# S202E.net
KiCad netlist of a schematic drawn in EAGLE
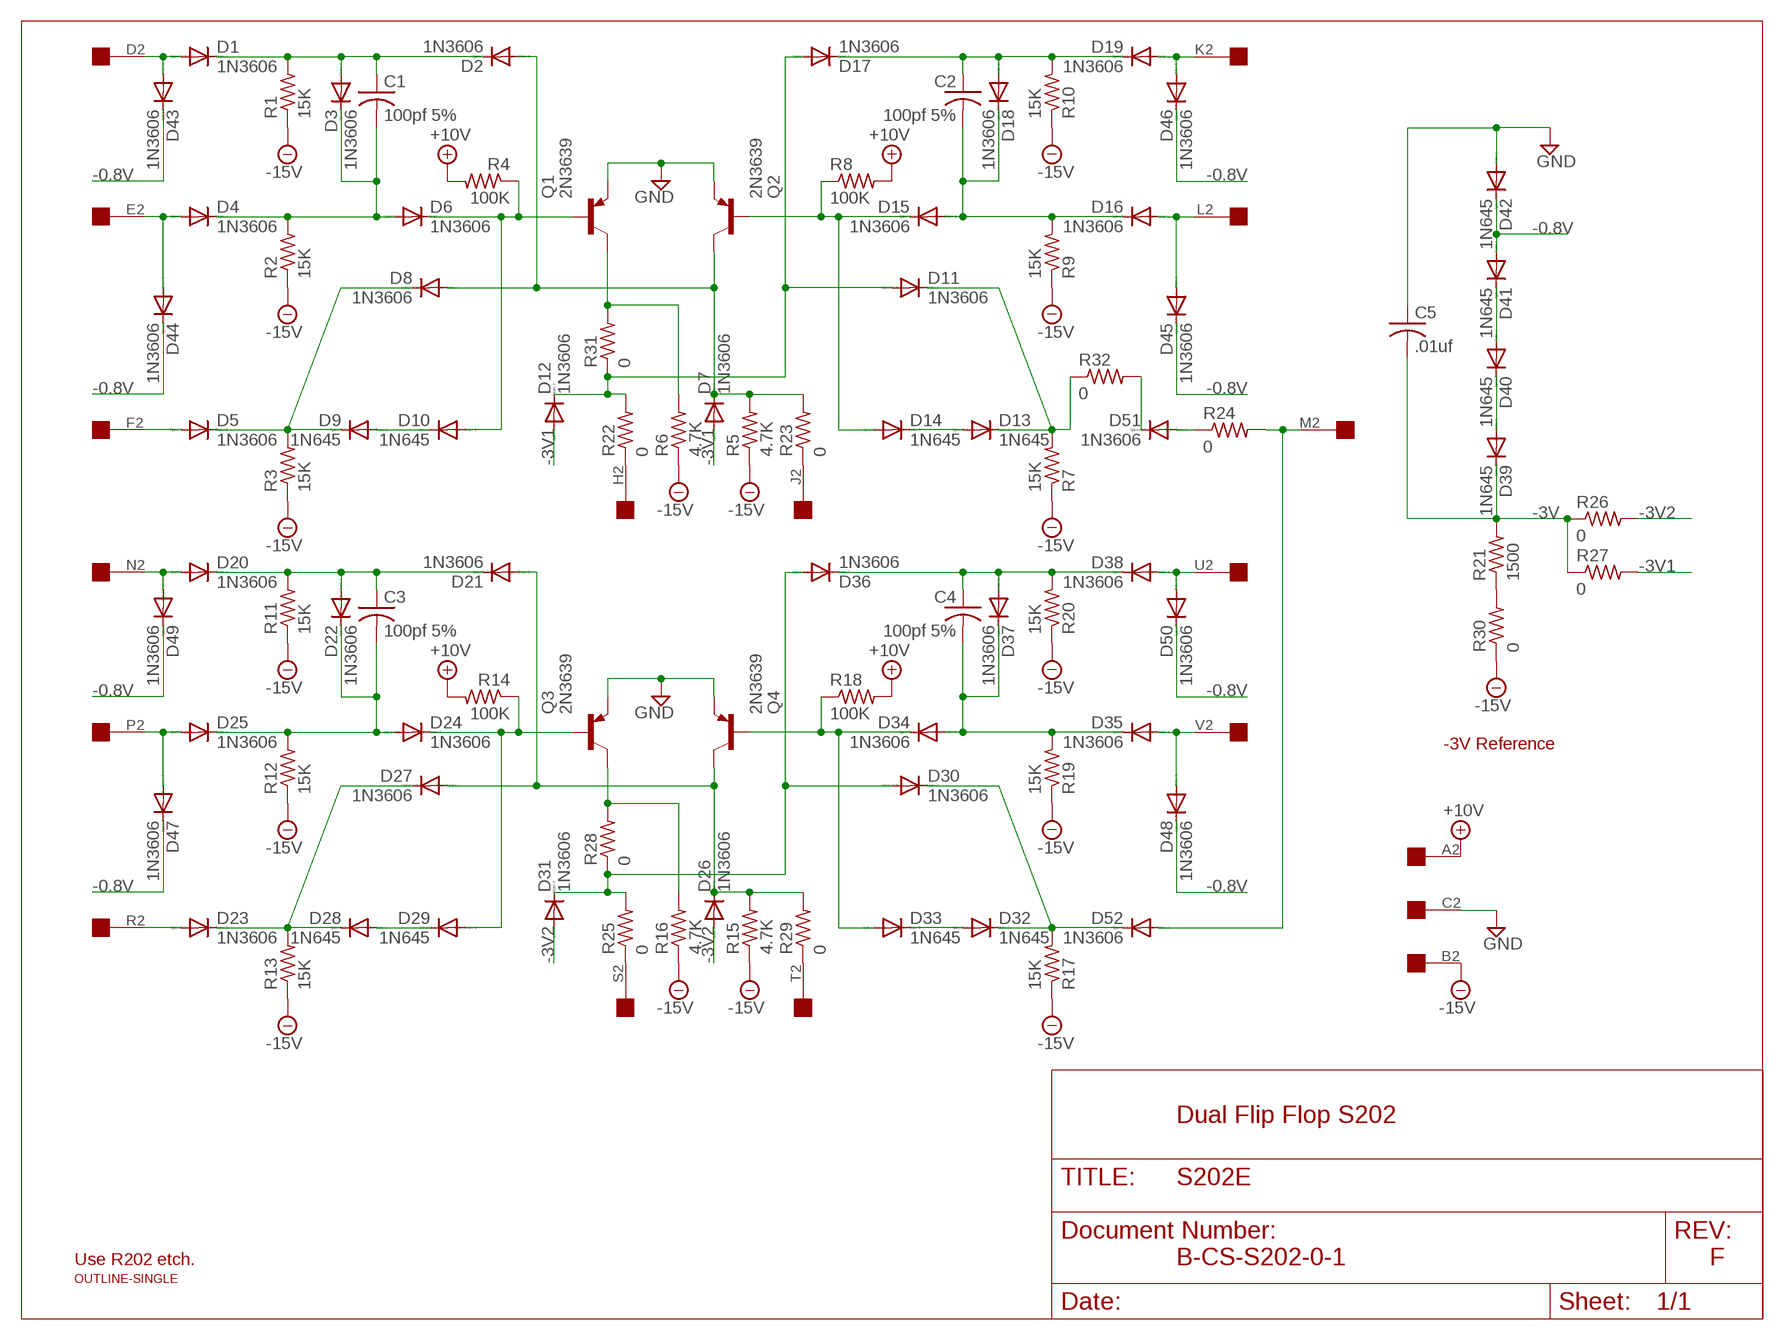
[diagram p0: schematic, sheet 1]

(export (version "E")
  (design (tool "Eeschema 10.0.6"))
  (components
    (comp (ref "C1")
      (value "100pf 5%")
      (footprint "eagle-import:C063-025X075")
      (libsource (lib "eagle-import") (part "C-US"))
    )
    (comp (ref "C2")
      (value "100pf 5%")
      (footprint "eagle-import:C063-025X075")
      (libsource (lib "eagle-import") (part "C-US"))
    )
    (comp (ref "C3")
      (value "100pf 5%")
      (footprint "eagle-import:C063-025X075")
      (libsource (lib "eagle-import") (part "C-US"))
    )
    (comp (ref "C4")
      (value "100pf 5%")
      (footprint "eagle-import:C063-025X075")
      (libsource (lib "eagle-import") (part "C-US"))
    )
    (comp (ref "C5")
      (value ".01uf")
      (footprint "eagle-import:C063-025X075")
      (libsource (lib "eagle-import") (part "C-US"))
    )
    (comp (ref "D1")
      (value "1N3606")
      (footprint "eagle-import:DO35-10")
      (libsource (lib "eagle-import") (part "1N4148DO35-10"))
    )
    (comp (ref "D2")
      (value "1N3606")
      (footprint "eagle-import:DO35-10")
      (libsource (lib "eagle-import") (part "1N4148DO35-10"))
    )
    (comp (ref "D3")
      (value "1N3606")
      (footprint "eagle-import:DO35-10")
      (libsource (lib "eagle-import") (part "1N4148DO35-10"))
    )
    (comp (ref "D4")
      (value "1N3606")
      (footprint "eagle-import:DO35-10")
      (libsource (lib "eagle-import") (part "1N4148DO35-10"))
    )
    (comp (ref "D5")
      (value "1N3606")
      (footprint "eagle-import:DO35-10")
      (libsource (lib "eagle-import") (part "1N4148DO35-10"))
    )
    (comp (ref "D6")
      (value "1N3606")
      (footprint "eagle-import:DO35-10")
      (libsource (lib "eagle-import") (part "1N4148DO35-10"))
    )
    (comp (ref "D7")
      (value "1N3606")
      (footprint "eagle-import:DO35-10")
      (libsource (lib "eagle-import") (part "1N4148DO35-10"))
    )
    (comp (ref "D8")
      (value "1N3606")
      (footprint "eagle-import:DO35-10")
      (libsource (lib "eagle-import") (part "1N4148DO35-10"))
    )
    (comp (ref "D9")
      (value "1N645")
      (footprint "eagle-import:DO35-10")
      (libsource (lib "eagle-import") (part "1N4148DO35-10"))
    )
    (comp (ref "D10")
      (value "1N645")
      (footprint "eagle-import:DO35-10")
      (libsource (lib "eagle-import") (part "1N4148DO35-10"))
    )
    (comp (ref "D11")
      (value "1N3606")
      (footprint "eagle-import:DO35-10")
      (libsource (lib "eagle-import") (part "1N4148DO35-10"))
    )
    (comp (ref "D12")
      (value "1N3606")
      (footprint "eagle-import:DO35-10")
      (libsource (lib "eagle-import") (part "1N4148DO35-10"))
    )
    (comp (ref "D13")
      (value "1N645")
      (footprint "eagle-import:DO35-10")
      (libsource (lib "eagle-import") (part "1N4148DO35-10"))
    )
    (comp (ref "D14")
      (value "1N645")
      (footprint "eagle-import:DO35-10")
      (libsource (lib "eagle-import") (part "1N4148DO35-10"))
    )
    (comp (ref "D15")
      (value "1N3606")
      (footprint "eagle-import:DO35-10")
      (libsource (lib "eagle-import") (part "1N4148DO35-10"))
    )
    (comp (ref "D16")
      (value "1N3606")
      (footprint "eagle-import:DO35-10")
      (libsource (lib "eagle-import") (part "1N4148DO35-10"))
    )
    (comp (ref "D17")
      (value "1N3606")
      (footprint "eagle-import:DO35-10")
      (libsource (lib "eagle-import") (part "1N4148DO35-10"))
    )
    (comp (ref "D18")
      (value "1N3606")
      (footprint "eagle-import:DO35-10")
      (libsource (lib "eagle-import") (part "1N4148DO35-10"))
    )
    (comp (ref "D19")
      (value "1N3606")
      (footprint "eagle-import:DO35-10")
      (libsource (lib "eagle-import") (part "1N4148DO35-10"))
    )
    (comp (ref "D20")
      (value "1N3606")
      (footprint "eagle-import:DO35-10")
      (libsource (lib "eagle-import") (part "1N4148DO35-10"))
    )
    (comp (ref "D21")
      (value "1N3606")
      (footprint "eagle-import:DO35-10")
      (libsource (lib "eagle-import") (part "1N4148DO35-10"))
    )
    (comp (ref "D22")
      (value "1N3606")
      (footprint "eagle-import:DO35-10")
      (libsource (lib "eagle-import") (part "1N4148DO35-10"))
    )
    (comp (ref "D23")
      (value "1N3606")
      (footprint "eagle-import:DO35-10")
      (libsource (lib "eagle-import") (part "1N4148DO35-10"))
    )
    (comp (ref "D24")
      (value "1N3606")
      (footprint "eagle-import:DO35-10")
      (libsource (lib "eagle-import") (part "1N4148DO35-10"))
    )
    (comp (ref "D25")
      (value "1N3606")
      (footprint "eagle-import:DO35-10")
      (libsource (lib "eagle-import") (part "1N4148DO35-10"))
    )
    (comp (ref "D26")
      (value "1N3606")
      (footprint "eagle-import:DO35-10")
      (libsource (lib "eagle-import") (part "1N4148DO35-10"))
    )
    (comp (ref "D27")
      (value "1N3606")
      (footprint "eagle-import:DO35-10")
      (libsource (lib "eagle-import") (part "1N4148DO35-10"))
    )
    (comp (ref "D28")
      (value "1N645")
      (footprint "eagle-import:DO35-10")
      (libsource (lib "eagle-import") (part "1N4148DO35-10"))
    )
    (comp (ref "D29")
      (value "1N645")
      (footprint "eagle-import:DO35-10")
      (libsource (lib "eagle-import") (part "1N4148DO35-10"))
    )
    (comp (ref "D30")
      (value "1N3606")
      (footprint "eagle-import:DO35-10")
      (libsource (lib "eagle-import") (part "1N4148DO35-10"))
    )
    (comp (ref "D31")
      (value "1N3606")
      (footprint "eagle-import:DO35-10")
      (libsource (lib "eagle-import") (part "1N4148DO35-10"))
    )
    (comp (ref "D32")
      (value "1N645")
      (footprint "eagle-import:DO35-10")
      (libsource (lib "eagle-import") (part "1N4148DO35-10"))
    )
    (comp (ref "D33")
      (value "1N645")
      (footprint "eagle-import:DO35-10")
      (libsource (lib "eagle-import") (part "1N4148DO35-10"))
    )
    (comp (ref "D34")
      (value "1N3606")
      (footprint "eagle-import:DO35-10")
      (libsource (lib "eagle-import") (part "1N4148DO35-10"))
    )
    (comp (ref "D35")
      (value "1N3606")
      (footprint "eagle-import:DO35-10")
      (libsource (lib "eagle-import") (part "1N4148DO35-10"))
    )
    (comp (ref "D36")
      (value "1N3606")
      (footprint "eagle-import:DO35-10")
      (libsource (lib "eagle-import") (part "1N4148DO35-10"))
    )
    (comp (ref "D37")
      (value "1N3606")
      (footprint "eagle-import:DO35-10")
      (libsource (lib "eagle-import") (part "1N4148DO35-10"))
    )
    (comp (ref "D38")
      (value "1N3606")
      (footprint "eagle-import:DO35-10")
      (libsource (lib "eagle-import") (part "1N4148DO35-10"))
    )
    (comp (ref "D39")
      (value "1N645")
      (footprint "eagle-import:DO35-10")
      (libsource (lib "eagle-import") (part "1N4148DO35-10"))
    )
    (comp (ref "D40")
      (value "1N645")
      (footprint "eagle-import:DO35-10")
      (libsource (lib "eagle-import") (part "1N4148DO35-10"))
    )
    (comp (ref "D41")
      (value "1N645")
      (footprint "eagle-import:DO35-10")
      (libsource (lib "eagle-import") (part "1N4148DO35-10"))
    )
    (comp (ref "D42")
      (value "1N645")
      (footprint "eagle-import:DO35-10")
      (libsource (lib "eagle-import") (part "1N4148DO35-10"))
    )
    (comp (ref "D43")
      (value "1N3606")
      (footprint "eagle-import:DO35-10")
      (libsource (lib "eagle-import") (part "1N4148DO35-10"))
    )
    (comp (ref "D44")
      (value "1N3606")
      (footprint "eagle-import:DO35-10")
      (libsource (lib "eagle-import") (part "1N4148DO35-10"))
    )
    (comp (ref "D45")
      (value "1N3606")
      (footprint "eagle-import:DO35-10")
      (libsource (lib "eagle-import") (part "1N4148DO35-10"))
    )
    (comp (ref "D46")
      (value "1N3606")
      (footprint "eagle-import:DO35-10")
      (libsource (lib "eagle-import") (part "1N4148DO35-10"))
    )
    (comp (ref "D47")
      (value "1N3606")
      (footprint "eagle-import:DO35-10")
      (libsource (lib "eagle-import") (part "1N4148DO35-10"))
    )
    (comp (ref "D48")
      (value "1N3606")
      (footprint "eagle-import:DO35-10")
      (libsource (lib "eagle-import") (part "1N4148DO35-10"))
    )
    (comp (ref "D49")
      (value "1N3606")
      (footprint "eagle-import:DO35-10")
      (libsource (lib "eagle-import") (part "1N4148DO35-10"))
    )
    (comp (ref "D50")
      (value "1N3606")
      (footprint "eagle-import:DO35-10")
      (libsource (lib "eagle-import") (part "1N4148DO35-10"))
    )
    (comp (ref "D51")
      (value "1N3606")
      (footprint "eagle-import:DO35-10")
      (libsource (lib "eagle-import") (part "1N4148DO35-10"))
    )
    (comp (ref "D52")
      (value "1N3606")
      (footprint "eagle-import:DO35-10")
      (libsource (lib "eagle-import") (part "1N4148DO35-10"))
    )
    (comp (ref "Q1")
      (value "2N3639")
      (footprint "eagle-import:TO39")
      (libsource (lib "eagle-import") (part "2N3637"))
    )
    (comp (ref "Q2")
      (value "2N3639")
      (footprint "eagle-import:TO39")
      (libsource (lib "eagle-import") (part "2N3637"))
    )
    (comp (ref "Q3")
      (value "2N3639")
      (footprint "eagle-import:TO39")
      (libsource (lib "eagle-import") (part "2N3637"))
    )
    (comp (ref "Q4")
      (value "2N3639")
      (footprint "eagle-import:TO39")
      (libsource (lib "eagle-import") (part "2N3637"))
    )
    (comp (ref "R1")
      (value "15K")
      (footprint "eagle-import:0207_10")
      (libsource (lib "eagle-import") (part "R-US_0207/10"))
    )
    (comp (ref "R2")
      (value "15K")
      (footprint "eagle-import:0207_10")
      (libsource (lib "eagle-import") (part "R-US_0207/10"))
    )
    (comp (ref "R3")
      (value "15K")
      (footprint "eagle-import:0207_10")
      (libsource (lib "eagle-import") (part "R-US_0207/10"))
    )
    (comp (ref "R4")
      (value "100K")
      (footprint "eagle-import:0207_10")
      (libsource (lib "eagle-import") (part "R-US_0207/10"))
    )
    (comp (ref "R5")
      (value "4.7K")
      (footprint "eagle-import:0207_10")
      (libsource (lib "eagle-import") (part "R-US_0207/10"))
    )
    (comp (ref "R6")
      (value "4.7K")
      (footprint "eagle-import:0207_10")
      (libsource (lib "eagle-import") (part "R-US_0207/10"))
    )
    (comp (ref "R7")
      (value "15K")
      (footprint "eagle-import:0207_10")
      (libsource (lib "eagle-import") (part "R-US_0207/10"))
    )
    (comp (ref "R8")
      (value "100K")
      (footprint "eagle-import:0207_10")
      (libsource (lib "eagle-import") (part "R-US_0207/10"))
    )
    (comp (ref "R9")
      (value "15K")
      (footprint "eagle-import:0207_10")
      (libsource (lib "eagle-import") (part "R-US_0207/10"))
    )
    (comp (ref "R10")
      (value "15K")
      (footprint "eagle-import:0207_10")
      (libsource (lib "eagle-import") (part "R-US_0207/10"))
    )
    (comp (ref "R11")
      (value "15K")
      (footprint "eagle-import:0207_10")
      (libsource (lib "eagle-import") (part "R-US_0207/10"))
    )
    (comp (ref "R12")
      (value "15K")
      (footprint "eagle-import:0207_10")
      (libsource (lib "eagle-import") (part "R-US_0207/10"))
    )
    (comp (ref "R13")
      (value "15K")
      (footprint "eagle-import:0207_10")
      (libsource (lib "eagle-import") (part "R-US_0207/10"))
    )
    (comp (ref "R14")
      (value "100K")
      (footprint "eagle-import:0207_10")
      (libsource (lib "eagle-import") (part "R-US_0207/10"))
    )
    (comp (ref "R15")
      (value "4.7K")
      (footprint "eagle-import:0207_10")
      (libsource (lib "eagle-import") (part "R-US_0207/10"))
    )
    (comp (ref "R16")
      (value "4.7K")
      (footprint "eagle-import:0207_10")
      (libsource (lib "eagle-import") (part "R-US_0207/10"))
    )
    (comp (ref "R17")
      (value "15K")
      (footprint "eagle-import:0207_10")
      (libsource (lib "eagle-import") (part "R-US_0207/10"))
    )
    (comp (ref "R18")
      (value "100K")
      (footprint "eagle-import:0207_10")
      (libsource (lib "eagle-import") (part "R-US_0207/10"))
    )
    (comp (ref "R19")
      (value "15K")
      (footprint "eagle-import:0207_10")
      (libsource (lib "eagle-import") (part "R-US_0207/10"))
    )
    (comp (ref "R20")
      (value "15K")
      (footprint "eagle-import:0207_10")
      (libsource (lib "eagle-import") (part "R-US_0207/10"))
    )
    (comp (ref "R21")
      (value "1500")
      (footprint "eagle-import:0207_10")
      (libsource (lib "eagle-import") (part "R-US_0207/10"))
    )
    (comp (ref "R22")
      (value "0")
      (footprint "eagle-import:0207_10")
      (libsource (lib "eagle-import") (part "R-US_0207/10"))
    )
    (comp (ref "R23")
      (value "0")
      (footprint "eagle-import:0207_10")
      (libsource (lib "eagle-import") (part "R-US_0207/10"))
    )
    (comp (ref "R24")
      (value "0")
      (footprint "eagle-import:0207_10")
      (libsource (lib "eagle-import") (part "R-US_0207/10"))
    )
    (comp (ref "R25")
      (value "0")
      (footprint "eagle-import:0207_10")
      (libsource (lib "eagle-import") (part "R-US_0207/10"))
    )
    (comp (ref "R26")
      (value "0")
      (footprint "eagle-import:0207_10")
      (libsource (lib "eagle-import") (part "R-US_0207/10"))
    )
    (comp (ref "R27")
      (value "0")
      (footprint "eagle-import:0207_10")
      (libsource (lib "eagle-import") (part "R-US_0207/10"))
    )
    (comp (ref "R28")
      (value "0")
      (footprint "eagle-import:0207_10")
      (libsource (lib "eagle-import") (part "R-US_0207/10"))
    )
    (comp (ref "R29")
      (value "0")
      (footprint "eagle-import:0207_10")
      (libsource (lib "eagle-import") (part "R-US_0207/10"))
    )
    (comp (ref "R30")
      (value "0")
      (footprint "eagle-import:0207_10")
      (libsource (lib "eagle-import") (part "R-US_0207/10"))
    )
    (comp (ref "R31")
      (value "0")
      (footprint "eagle-import:0207_10")
      (libsource (lib "eagle-import") (part "R-US_0207/10"))
    )
    (comp (ref "R32")
      (value "0")
      (footprint "eagle-import:0207_10")
      (libsource (lib "eagle-import") (part "R-US_0207/10"))
    )
    (comp (ref "U$1")
      (value "OUTLINE-SINGLE")
      (footprint "eagle-import:SINGLE")
      (libsource (lib "eagle-import") (part "OUTLINE-SINGLE"))
    )
    (comp (ref "U$2")
      (value "EDGE-1")
      (footprint "eagle-import:EDGE-CON1")
      (libsource (lib "eagle-import") (part "EDGE-1"))
    )
  )
  (nets
    (net (code "1") (name "+10V") (class "Default")
      (node (ref "R14") (pin "2") (pinfunction "2_2") (pintype "passive"))
      (node (ref "R18") (pin "2") (pinfunction "2_2") (pintype "passive"))
      (node (ref "R4") (pin "2") (pinfunction "2_2") (pintype "passive"))
      (node (ref "R8") (pin "2") (pinfunction "2_2") (pintype "passive"))
      (node (ref "U$2") (pin "A2") (pinfunction "1_A2") (pintype "bidirectional"))
    )
    (net (code "2") (name "-15V") (class "Default")
      (node (ref "R1") (pin "1") (pinfunction "1_1") (pintype "passive"))
      (node (ref "R10") (pin "1") (pinfunction "1_1") (pintype "passive"))
      (node (ref "R11") (pin "1") (pinfunction "1_1") (pintype "passive"))
      (node (ref "R12") (pin "1") (pinfunction "1_1") (pintype "passive"))
      (node (ref "R13") (pin "1") (pinfunction "1_1") (pintype "passive"))
      (node (ref "R15") (pin "1") (pinfunction "1_1") (pintype "passive"))
      (node (ref "R16") (pin "1") (pinfunction "1_1") (pintype "passive"))
      (node (ref "R17") (pin "1") (pinfunction "1_1") (pintype "passive"))
      (node (ref "R19") (pin "1") (pinfunction "1_1") (pintype "passive"))
      (node (ref "R2") (pin "1") (pinfunction "1_1") (pintype "passive"))
      (node (ref "R20") (pin "1") (pinfunction "1_1") (pintype "passive"))
      (node (ref "R3") (pin "1") (pinfunction "1_1") (pintype "passive"))
      (node (ref "R30") (pin "1") (pinfunction "1_1") (pintype "passive"))
      (node (ref "R5") (pin "1") (pinfunction "1_1") (pintype "passive"))
      (node (ref "R6") (pin "1") (pinfunction "1_1") (pintype "passive"))
      (node (ref "R7") (pin "1") (pinfunction "1_1") (pintype "passive"))
      (node (ref "R9") (pin "1") (pinfunction "1_1") (pintype "passive"))
      (node (ref "U$2") (pin "B2") (pinfunction "1_B2") (pintype "bidirectional"))
    )
    (net (code "3") (name "/-0.8V") (class "Default")
      (node (ref "D41") (pin "A") (pinfunction "A_A") (pintype "passive"))
      (node (ref "D42") (pin "C") (pinfunction "C_C") (pintype "passive"))
      (node (ref "D43") (pin "C") (pinfunction "C_C") (pintype "passive"))
      (node (ref "D44") (pin "C") (pinfunction "C_C") (pintype "passive"))
      (node (ref "D45") (pin "C") (pinfunction "C_C") (pintype "passive"))
      (node (ref "D46") (pin "C") (pinfunction "C_C") (pintype "passive"))
      (node (ref "D47") (pin "C") (pinfunction "C_C") (pintype "passive"))
      (node (ref "D48") (pin "C") (pinfunction "C_C") (pintype "passive"))
      (node (ref "D49") (pin "C") (pinfunction "C_C") (pintype "passive"))
      (node (ref "D50") (pin "C") (pinfunction "C_C") (pintype "passive"))
    )
    (net (code "4") (name "/-3V") (class "Default")
      (node (ref "C5") (pin "2") (pinfunction "2_2") (pintype "passive"))
      (node (ref "D39") (pin "C") (pinfunction "C_C") (pintype "passive"))
      (node (ref "R21") (pin "2") (pinfunction "2_2") (pintype "passive"))
      (node (ref "R26") (pin "1") (pinfunction "1_1") (pintype "passive"))
      (node (ref "R27") (pin "1") (pinfunction "1_1") (pintype "passive"))
    )
    (net (code "5") (name "/-3V1") (class "Default")
      (node (ref "D12") (pin "A") (pinfunction "A_A") (pintype "passive"))
      (node (ref "D7") (pin "A") (pinfunction "A_A") (pintype "passive"))
      (node (ref "R27") (pin "2") (pinfunction "2_2") (pintype "passive"))
    )
    (net (code "6") (name "/-3V2") (class "Default")
      (node (ref "D26") (pin "A") (pinfunction "A_A") (pintype "passive"))
      (node (ref "D31") (pin "A") (pinfunction "A_A") (pintype "passive"))
      (node (ref "R26") (pin "2") (pinfunction "2_2") (pintype "passive"))
    )
    (net (code "7") (name "GND") (class "Default")
      (node (ref "C5") (pin "1") (pinfunction "1_1") (pintype "passive"))
      (node (ref "D42") (pin "A") (pinfunction "A_A") (pintype "passive"))
      (node (ref "Q1") (pin "1") (pinfunction "E_1") (pintype "passive"))
      (node (ref "Q2") (pin "1") (pinfunction "E_1") (pintype "passive"))
      (node (ref "Q3") (pin "1") (pinfunction "E_1") (pintype "passive"))
      (node (ref "Q4") (pin "1") (pinfunction "E_1") (pintype "passive"))
      (node (ref "U$2") (pin "C2") (pinfunction "1_C2") (pintype "bidirectional"))
    )
    (net (code "8") (name "Net-(C1-Pad1)") (class "Default")
      (node (ref "C1") (pin "1") (pinfunction "1_1") (pintype "passive"))
      (node (ref "D1") (pin "C") (pinfunction "C_C") (pintype "passive"))
      (node (ref "D2") (pin "C") (pinfunction "C_C") (pintype "passive"))
      (node (ref "D3") (pin "A") (pinfunction "A_A") (pintype "passive"))
      (node (ref "R1") (pin "2") (pinfunction "2_2") (pintype "passive"))
    )
    (net (code "9") (name "Net-(C1-Pad2)") (class "Default")
      (node (ref "C1") (pin "2") (pinfunction "2_2") (pintype "passive"))
      (node (ref "D3") (pin "C") (pinfunction "C_C") (pintype "passive"))
      (node (ref "D4") (pin "C") (pinfunction "C_C") (pintype "passive"))
      (node (ref "D6") (pin "A") (pinfunction "A_A") (pintype "passive"))
      (node (ref "R2") (pin "2") (pinfunction "2_2") (pintype "passive"))
    )
    (net (code "10") (name "Net-(C2-Pad1)") (class "Default")
      (node (ref "C2") (pin "1") (pinfunction "1_1") (pintype "passive"))
      (node (ref "D17") (pin "C") (pinfunction "C_C") (pintype "passive"))
      (node (ref "D18") (pin "A") (pinfunction "A_A") (pintype "passive"))
      (node (ref "D19") (pin "C") (pinfunction "C_C") (pintype "passive"))
      (node (ref "R10") (pin "2") (pinfunction "2_2") (pintype "passive"))
    )
    (net (code "11") (name "Net-(C2-Pad2)") (class "Default")
      (node (ref "C2") (pin "2") (pinfunction "2_2") (pintype "passive"))
      (node (ref "D15") (pin "A") (pinfunction "A_A") (pintype "passive"))
      (node (ref "D16") (pin "C") (pinfunction "C_C") (pintype "passive"))
      (node (ref "D18") (pin "C") (pinfunction "C_C") (pintype "passive"))
      (node (ref "R9") (pin "2") (pinfunction "2_2") (pintype "passive"))
    )
    (net (code "12") (name "Net-(C3-Pad1)") (class "Default")
      (node (ref "C3") (pin "1") (pinfunction "1_1") (pintype "passive"))
      (node (ref "D20") (pin "C") (pinfunction "C_C") (pintype "passive"))
      (node (ref "D21") (pin "C") (pinfunction "C_C") (pintype "passive"))
      (node (ref "D22") (pin "A") (pinfunction "A_A") (pintype "passive"))
      (node (ref "R11") (pin "2") (pinfunction "2_2") (pintype "passive"))
    )
    (net (code "13") (name "Net-(C3-Pad2)") (class "Default")
      (node (ref "C3") (pin "2") (pinfunction "2_2") (pintype "passive"))
      (node (ref "D22") (pin "C") (pinfunction "C_C") (pintype "passive"))
      (node (ref "D24") (pin "A") (pinfunction "A_A") (pintype "passive"))
      (node (ref "D25") (pin "C") (pinfunction "C_C") (pintype "passive"))
      (node (ref "R12") (pin "2") (pinfunction "2_2") (pintype "passive"))
    )
    (net (code "14") (name "Net-(C4-Pad1)") (class "Default")
      (node (ref "C4") (pin "1") (pinfunction "1_1") (pintype "passive"))
      (node (ref "D36") (pin "C") (pinfunction "C_C") (pintype "passive"))
      (node (ref "D37") (pin "A") (pinfunction "A_A") (pintype "passive"))
      (node (ref "D38") (pin "C") (pinfunction "C_C") (pintype "passive"))
      (node (ref "R20") (pin "2") (pinfunction "2_2") (pintype "passive"))
    )
    (net (code "15") (name "Net-(C4-Pad2)") (class "Default")
      (node (ref "C4") (pin "2") (pinfunction "2_2") (pintype "passive"))
      (node (ref "D34") (pin "A") (pinfunction "A_A") (pintype "passive"))
      (node (ref "D35") (pin "C") (pinfunction "C_C") (pintype "passive"))
      (node (ref "D37") (pin "C") (pinfunction "C_C") (pintype "passive"))
      (node (ref "R19") (pin "2") (pinfunction "2_2") (pintype "passive"))
    )
    (net (code "16") (name "Net-(D5-PadC)") (class "Default")
      (node (ref "D5") (pin "C") (pinfunction "C_C") (pintype "passive"))
      (node (ref "D8") (pin "C") (pinfunction "C_C") (pintype "passive"))
      (node (ref "D9") (pin "C") (pinfunction "C_C") (pintype "passive"))
      (node (ref "R3") (pin "2") (pinfunction "2_2") (pintype "passive"))
    )
    (net (code "17") (name "Net-(D10-PadC)") (class "Default")
      (node (ref "D10") (pin "C") (pinfunction "C_C") (pintype "passive"))
      (node (ref "D9") (pin "A") (pinfunction "A_A") (pintype "passive"))
    )
    (net (code "18") (name "Net-(D11-PadA)") (class "Default")
      (node (ref "D11") (pin "A") (pinfunction "A_A") (pintype "passive"))
      (node (ref "D12") (pin "C") (pinfunction "C_C") (pintype "passive"))
      (node (ref "D17") (pin "A") (pinfunction "A_A") (pintype "passive"))
      (node (ref "R22") (pin "2") (pinfunction "2_2") (pintype "passive"))
      (node (ref "R31") (pin "1") (pinfunction "1_1") (pintype "passive"))
    )
    (net (code "19") (name "Net-(D11-PadC)") (class "Default")
      (node (ref "D11") (pin "C") (pinfunction "C_C") (pintype "passive"))
      (node (ref "D13") (pin "C") (pinfunction "C_C") (pintype "passive"))
      (node (ref "R32") (pin "1") (pinfunction "1_1") (pintype "passive"))
      (node (ref "R7") (pin "2") (pinfunction "2_2") (pintype "passive"))
    )
    (net (code "20") (name "Net-(D13-PadA)") (class "Default")
      (node (ref "D13") (pin "A") (pinfunction "A_A") (pintype "passive"))
      (node (ref "D14") (pin "C") (pinfunction "C_C") (pintype "passive"))
    )
    (net (code "21") (name "Net-(D23-PadC)") (class "Default")
      (node (ref "D23") (pin "C") (pinfunction "C_C") (pintype "passive"))
      (node (ref "D27") (pin "C") (pinfunction "C_C") (pintype "passive"))
      (node (ref "D28") (pin "C") (pinfunction "C_C") (pintype "passive"))
      (node (ref "R13") (pin "2") (pinfunction "2_2") (pintype "passive"))
    )
    (net (code "22") (name "Net-(D28-PadA)") (class "Default")
      (node (ref "D28") (pin "A") (pinfunction "A_A") (pintype "passive"))
      (node (ref "D29") (pin "C") (pinfunction "C_C") (pintype "passive"))
    )
    (net (code "23") (name "Net-(D30-PadA)") (class "Default")
      (node (ref "D30") (pin "A") (pinfunction "A_A") (pintype "passive"))
      (node (ref "D31") (pin "C") (pinfunction "C_C") (pintype "passive"))
      (node (ref "D36") (pin "A") (pinfunction "A_A") (pintype "passive"))
      (node (ref "R25") (pin "2") (pinfunction "2_2") (pintype "passive"))
      (node (ref "R28") (pin "1") (pinfunction "1_1") (pintype "passive"))
    )
    (net (code "24") (name "Net-(D30-PadC)") (class "Default")
      (node (ref "D30") (pin "C") (pinfunction "C_C") (pintype "passive"))
      (node (ref "D32") (pin "C") (pinfunction "C_C") (pintype "passive"))
      (node (ref "D52") (pin "C") (pinfunction "C_C") (pintype "passive"))
      (node (ref "R17") (pin "2") (pinfunction "2_2") (pintype "passive"))
    )
    (net (code "25") (name "Net-(D32-PadA)") (class "Default")
      (node (ref "D32") (pin "A") (pinfunction "A_A") (pintype "passive"))
      (node (ref "D33") (pin "C") (pinfunction "C_C") (pintype "passive"))
    )
    (net (code "26") (name "Net-(D39-PadA)") (class "Default")
      (node (ref "D39") (pin "A") (pinfunction "A_A") (pintype "passive"))
      (node (ref "D40") (pin "C") (pinfunction "C_C") (pintype "passive"))
    )
    (net (code "27") (name "Net-(D40-PadA)") (class "Default")
      (node (ref "D40") (pin "A") (pinfunction "A_A") (pintype "passive"))
      (node (ref "D41") (pin "C") (pinfunction "C_C") (pintype "passive"))
    )
    (net (code "28") (name "Net-(D51-PadA)") (class "Default")
      (node (ref "D51") (pin "A") (pinfunction "A_A") (pintype "passive"))
      (node (ref "R24") (pin "1") (pinfunction "1_1") (pintype "passive"))
    )
    (net (code "29") (name "Net-(D51-PadC)") (class "Default")
      (node (ref "D51") (pin "C") (pinfunction "C_C") (pintype "passive"))
      (node (ref "R32") (pin "2") (pinfunction "2_2") (pintype "passive"))
    )
    (net (code "30") (name "Net-(Q1-B)") (class "Default")
      (node (ref "D10") (pin "A") (pinfunction "A_A") (pintype "passive"))
      (node (ref "D6") (pin "C") (pinfunction "C_C") (pintype "passive"))
      (node (ref "Q1") (pin "2") (pinfunction "B_2") (pintype "passive"))
      (node (ref "R4") (pin "1") (pinfunction "1_1") (pintype "passive"))
    )
    (net (code "31") (name "Net-(Q1-C)") (class "Default")
      (node (ref "Q1") (pin "3") (pinfunction "C_3") (pintype "passive"))
      (node (ref "R31") (pin "2") (pinfunction "2_2") (pintype "passive"))
      (node (ref "R6") (pin "2") (pinfunction "2_2") (pintype "passive"))
    )
    (net (code "32") (name "Net-(Q2-B)") (class "Default")
      (node (ref "D14") (pin "A") (pinfunction "A_A") (pintype "passive"))
      (node (ref "D15") (pin "C") (pinfunction "C_C") (pintype "passive"))
      (node (ref "Q2") (pin "2") (pinfunction "B_2") (pintype "passive"))
      (node (ref "R8") (pin "1") (pinfunction "1_1") (pintype "passive"))
    )
    (net (code "33") (name "Net-(Q2-C)") (class "Default")
      (node (ref "D2") (pin "A") (pinfunction "A_A") (pintype "passive"))
      (node (ref "D7") (pin "C") (pinfunction "C_C") (pintype "passive"))
      (node (ref "D8") (pin "A") (pinfunction "A_A") (pintype "passive"))
      (node (ref "Q2") (pin "3") (pinfunction "C_3") (pintype "passive"))
      (node (ref "R23") (pin "2") (pinfunction "2_2") (pintype "passive"))
      (node (ref "R5") (pin "2") (pinfunction "2_2") (pintype "passive"))
    )
    (net (code "34") (name "Net-(Q3-B)") (class "Default")
      (node (ref "D24") (pin "C") (pinfunction "C_C") (pintype "passive"))
      (node (ref "D29") (pin "A") (pinfunction "A_A") (pintype "passive"))
      (node (ref "Q3") (pin "2") (pinfunction "B_2") (pintype "passive"))
      (node (ref "R14") (pin "1") (pinfunction "1_1") (pintype "passive"))
    )
    (net (code "35") (name "Net-(Q3-C)") (class "Default")
      (node (ref "Q3") (pin "3") (pinfunction "C_3") (pintype "passive"))
      (node (ref "R16") (pin "2") (pinfunction "2_2") (pintype "passive"))
      (node (ref "R28") (pin "2") (pinfunction "2_2") (pintype "passive"))
    )
    (net (code "36") (name "Net-(Q4-B)") (class "Default")
      (node (ref "D33") (pin "A") (pinfunction "A_A") (pintype "passive"))
      (node (ref "D34") (pin "C") (pinfunction "C_C") (pintype "passive"))
      (node (ref "Q4") (pin "2") (pinfunction "B_2") (pintype "passive"))
      (node (ref "R18") (pin "1") (pinfunction "1_1") (pintype "passive"))
    )
    (net (code "37") (name "Net-(Q4-C)") (class "Default")
      (node (ref "D21") (pin "A") (pinfunction "A_A") (pintype "passive"))
      (node (ref "D26") (pin "C") (pinfunction "C_C") (pintype "passive"))
      (node (ref "D27") (pin "A") (pinfunction "A_A") (pintype "passive"))
      (node (ref "Q4") (pin "3") (pinfunction "C_3") (pintype "passive"))
      (node (ref "R15") (pin "2") (pinfunction "2_2") (pintype "passive"))
      (node (ref "R29") (pin "2") (pinfunction "2_2") (pintype "passive"))
    )
    (net (code "38") (name "Net-(R21-Pad1)") (class "Default")
      (node (ref "R21") (pin "1") (pinfunction "1_1") (pintype "passive"))
      (node (ref "R30") (pin "2") (pinfunction "2_2") (pintype "passive"))
    )
    (net (code "39") (name "Net-(U$2D-1)") (class "Default")
      (node (ref "D1") (pin "A") (pinfunction "A_A") (pintype "passive"))
      (node (ref "D43") (pin "A") (pinfunction "A_A") (pintype "passive"))
      (node (ref "U$2") (pin "D2") (pinfunction "1_D2") (pintype "bidirectional"))
    )
    (net (code "40") (name "Net-(U$2E-1)") (class "Default")
      (node (ref "D4") (pin "A") (pinfunction "A_A") (pintype "passive"))
      (node (ref "D44") (pin "A") (pinfunction "A_A") (pintype "passive"))
      (node (ref "U$2") (pin "E2") (pinfunction "1_E2") (pintype "bidirectional"))
    )
    (net (code "41") (name "Net-(U$2F-1)") (class "Default")
      (node (ref "D5") (pin "A") (pinfunction "A_A") (pintype "passive"))
      (node (ref "U$2") (pin "F2") (pinfunction "1_F2") (pintype "bidirectional"))
    )
    (net (code "42") (name "Net-(U$2G-1)") (class "Default")
      (node (ref "R22") (pin "1") (pinfunction "1_1") (pintype "passive"))
      (node (ref "U$2") (pin "H2") (pinfunction "1_H2") (pintype "bidirectional"))
    )
    (net (code "43") (name "Net-(U$2H-1)") (class "Default")
      (node (ref "R23") (pin "1") (pinfunction "1_1") (pintype "passive"))
      (node (ref "U$2") (pin "J2") (pinfunction "1_J2") (pintype "bidirectional"))
    )
    (net (code "44") (name "Net-(U$2I-1)") (class "Default")
      (node (ref "D19") (pin "A") (pinfunction "A_A") (pintype "passive"))
      (node (ref "D46") (pin "A") (pinfunction "A_A") (pintype "passive"))
      (node (ref "U$2") (pin "K2") (pinfunction "1_K2") (pintype "bidirectional"))
    )
    (net (code "45") (name "Net-(U$2J-1)") (class "Default")
      (node (ref "D16") (pin "A") (pinfunction "A_A") (pintype "passive"))
      (node (ref "D45") (pin "A") (pinfunction "A_A") (pintype "passive"))
      (node (ref "U$2") (pin "L2") (pinfunction "1_L2") (pintype "bidirectional"))
    )
    (net (code "46") (name "Net-(U$2K-1)") (class "Default")
      (node (ref "D52") (pin "A") (pinfunction "A_A") (pintype "passive"))
      (node (ref "R24") (pin "2") (pinfunction "2_2") (pintype "passive"))
      (node (ref "U$2") (pin "M2") (pinfunction "1_M2") (pintype "bidirectional"))
    )
    (net (code "47") (name "Net-(U$2L-1)") (class "Default")
      (node (ref "D20") (pin "A") (pinfunction "A_A") (pintype "passive"))
      (node (ref "D49") (pin "A") (pinfunction "A_A") (pintype "passive"))
      (node (ref "U$2") (pin "N2") (pinfunction "1_N2") (pintype "bidirectional"))
    )
    (net (code "48") (name "Net-(U$2M-1)") (class "Default")
      (node (ref "D25") (pin "A") (pinfunction "A_A") (pintype "passive"))
      (node (ref "D47") (pin "A") (pinfunction "A_A") (pintype "passive"))
      (node (ref "U$2") (pin "P2") (pinfunction "1_P2") (pintype "bidirectional"))
    )
    (net (code "49") (name "Net-(U$2N-1)") (class "Default")
      (node (ref "D23") (pin "A") (pinfunction "A_A") (pintype "passive"))
      (node (ref "U$2") (pin "R2") (pinfunction "1_R2") (pintype "bidirectional"))
    )
    (net (code "50") (name "Net-(U$2O-1)") (class "Default")
      (node (ref "R25") (pin "1") (pinfunction "1_1") (pintype "passive"))
      (node (ref "U$2") (pin "S2") (pinfunction "1_S2") (pintype "bidirectional"))
    )
    (net (code "51") (name "Net-(U$2P-1)") (class "Default")
      (node (ref "R29") (pin "1") (pinfunction "1_1") (pintype "passive"))
      (node (ref "U$2") (pin "T2") (pinfunction "1_T2") (pintype "bidirectional"))
    )
    (net (code "52") (name "Net-(U$2Q-1)") (class "Default")
      (node (ref "D38") (pin "A") (pinfunction "A_A") (pintype "passive"))
      (node (ref "D50") (pin "A") (pinfunction "A_A") (pintype "passive"))
      (node (ref "U$2") (pin "U2") (pinfunction "1_U2") (pintype "bidirectional"))
    )
    (net (code "53") (name "Net-(U$2R-1)") (class "Default")
      (node (ref "D35") (pin "A") (pinfunction "A_A") (pintype "passive"))
      (node (ref "D48") (pin "A") (pinfunction "A_A") (pintype "passive"))
      (node (ref "U$2") (pin "V2") (pinfunction "1_V2") (pintype "bidirectional"))
    )
  )
)
